# IoT_Indoor_Climate_Sensor-_upgraded.net
KiCad netlist of a schematic drawn in EasyEDA
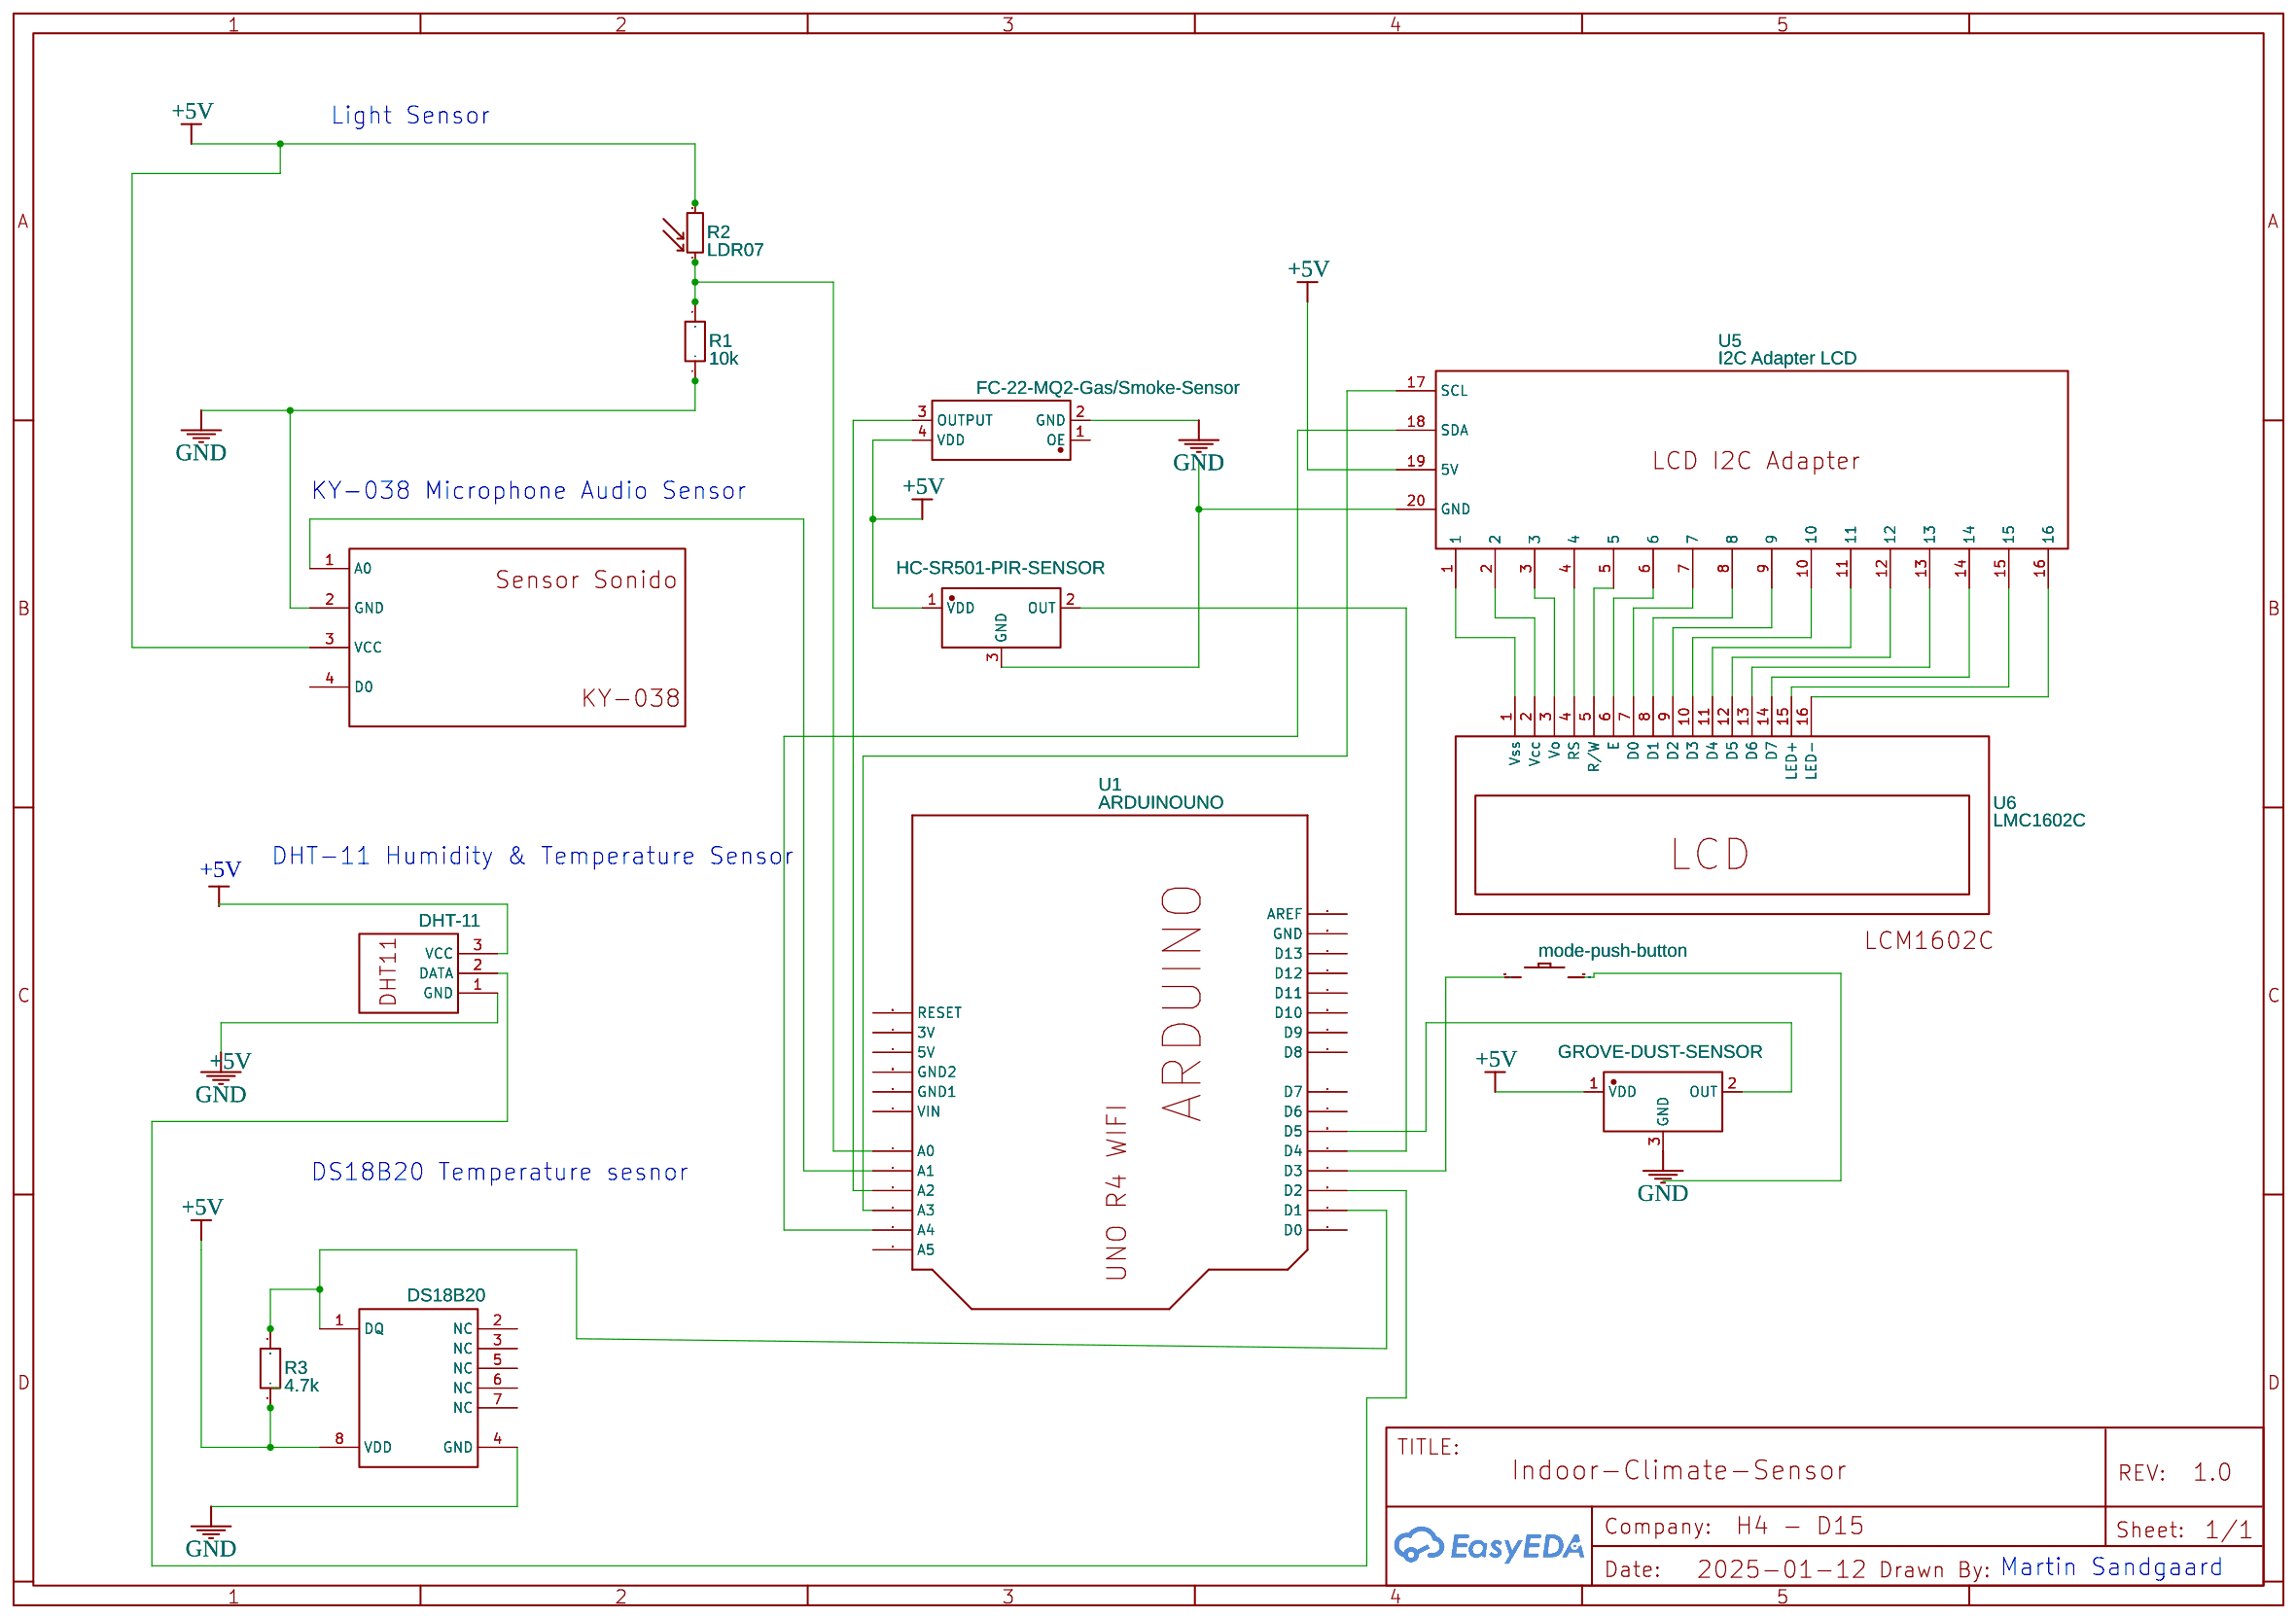
[diagram p0: schematic sheet]

(export (version "E")
  (design (tool "Eeschema 10.0.6"))
  (components
    (comp (ref "1") (value "mode-push-button") (libsource (lib "") (part "button")))
    (comp (ref "GROVE-DUST-SENSOR")
      (value "EKMB1309113K")
      (fields (field (name "Manufacturer") "PANASONIC(松下)"))
      (libsource (lib "") (part "EKMB1309113K_1"))
    )
    (comp (ref "HC-SR501-PIR-SENSOR")
      (value "EKMB1309113K")
      (fields (field (name "Manufacturer") "PANASONIC(松下)"))
      (libsource (lib "") (part "EKMB1309113K"))
    )
    (comp (ref "OSC1")
      (value "FC-22-MQ2-Gas/Smoke-Sensor")
      (fields (field (name "Manufacturer Part") "AMPMDFC-22.0000T3") (field (name "Manufacturer") "ABRACON"))
      (libsource (lib "") (part "AMPMDFC-22.0000T3"))
    )
    (comp (ref "R1") (value "10k") (libsource (lib "") (part "R_0603_EU")))
    (comp (ref "R2") (value "LDR07") (libsource (lib "") (part "LDR07")))
    (comp (ref "R3") (value "4.7k") (libsource (lib "") (part "R_0603_EU")))
    (comp (ref "U1") (value "ARDUINOUNO") (libsource (lib "") (part "ARDUINOUNO")))
    (comp (ref "U2") (value "DS18B20") (libsource (lib "") (part "DS18B20U+")))
    (comp (ref "U3")
      (value "KY-038 Microphone Sound Sensor")
      (libsource (lib "") (part "KY-037 KY038 SENSOR SONIDO COPY"))
    )
    (comp (ref "U4") (value "DHT-11") (libsource (lib "") (part "DHT-11")))
    (comp (ref "U5") (value "I2C Adapter LCD") (libsource (lib "") (part "I2C Adapter LCD")))
    (comp (ref "U6") (value "LMC1602C") (libsource (lib "") (part "LMC1602C")))
  )
  (nets
    (net (code "1") (name "+5V") (class "Default")
      (node (ref "GROVE-DUST-SENSOR") (pin "1") (pinfunction "VDD_1") (pintype "unspecified"))
      (node (ref "HC-SR501-PIR-SENSOR") (pin "1") (pinfunction "VDD_1") (pintype "unspecified"))
      (node (ref "OSC1") (pin "4") (pinfunction "VDD_4") (pintype "unspecified"))
      (node (ref "R2") (pin "1") (pintype "unspecified"))
      (node (ref "R3") (pin "1") (pinfunction "1_1") (pintype "unspecified"))
      (node (ref "U2") (pin "8") (pinfunction "VDD_8") (pintype "passive"))
      (node (ref "U3") (pin "3") (pinfunction "VCC_3") (pintype "unspecified"))
      (node (ref "U4") (pin "3") (pinfunction "VCC_3") (pintype "unspecified"))
      (node (ref "U5") (pin "19") (pinfunction "5V_19") (pintype "unspecified"))
    )
    (net (code "2") (name "GND") (class "Default")
      (node (ref "GROVE-DUST-SENSOR") (pin "3") (pinfunction "GND_3") (pintype "unspecified"))
      (node (ref "OSC1") (pin "2") (pinfunction "GND_2") (pintype "unspecified"))
      (node (ref "R1") (pin "1") (pinfunction "1_1") (pintype "unspecified"))
      (node (ref "U2") (pin "4") (pinfunction "GND_4") (pintype "passive"))
      (node (ref "U3") (pin "2") (pinfunction "GND_2") (pintype "unspecified"))
      (node (ref "U4") (pin "1") (pinfunction "GND_1") (pintype "unspecified"))
    )
    (net (code "3") (name "Net-(1-PadP$GND)") (class "Default")
      (node (ref "1") (pin "P$GND") (pinfunction "P$GND_P$GND") (pintype "unspecified"))
      (node (ref "U1") (pin "D3") (pinfunction "D3_D3") (pintype "unspecified"))
    )
    (net (code "4") (name "Net-(GROVE-DUST-SENSOR-OUT)") (class "Default")
      (node (ref "GROVE-DUST-SENSOR") (pin "2") (pinfunction "OUT_2") (pintype "unspecified"))
      (node (ref "U1") (pin "D5") (pinfunction "D5_D5") (pintype "unspecified"))
    )
    (net (code "5") (name "Net-(HC-SR501-PIR-SENSOR-GND)") (class "Default")
      (node (ref "HC-SR501-PIR-SENSOR") (pin "3") (pinfunction "GND_3") (pintype "unspecified"))
      (node (ref "U5") (pin "20") (pinfunction "GND_20") (pintype "unspecified"))
    )
    (net (code "6") (name "Net-(HC-SR501-PIR-SENSOR-OUT)") (class "Default")
      (node (ref "HC-SR501-PIR-SENSOR") (pin "2") (pinfunction "OUT_2") (pintype "unspecified"))
      (node (ref "U1") (pin "D4") (pinfunction "D4_D4") (pintype "unspecified"))
    )
    (net (code "7") (name "Net-(OSC1-OUTPUT)") (class "Default")
      (node (ref "OSC1") (pin "3") (pinfunction "OUTPUT_3") (pintype "unspecified"))
      (node (ref "U1") (pin "A2") (pinfunction "A2_A2") (pintype "unspecified"))
    )
    (net (code "8") (name "Net-(R1-Pad2)") (class "Default")
      (node (ref "R1") (pin "2") (pinfunction "2_2") (pintype "unspecified"))
      (node (ref "R2") (pin "2") (pintype "unspecified"))
      (node (ref "U1") (pin "A0") (pinfunction "A0_A0") (pintype "unspecified"))
    )
    (net (code "9") (name "Net-(U2-DQ)") (class "Default")
      (node (ref "R3") (pin "2") (pinfunction "2_2") (pintype "unspecified"))
      (node (ref "U1") (pin "D1") (pinfunction "D1_D1") (pintype "unspecified"))
      (node (ref "U2") (pin "1") (pinfunction "DQ_1") (pintype "bidirectional"))
    )
    (net (code "10") (name "Net-(U3-A0)") (class "Default")
      (node (ref "U1") (pin "A1") (pinfunction "A1_A1") (pintype "unspecified"))
      (node (ref "U3") (pin "1") (pinfunction "A0_1") (pintype "unspecified"))
    )
    (net (code "11") (name "Net-(U4-DATA)") (class "Default")
      (node (ref "U1") (pin "D2") (pinfunction "D2_D2") (pintype "unspecified"))
      (node (ref "U4") (pin "2") (pinfunction "DATA_2") (pintype "unspecified"))
    )
    (net (code "12") (name "Net-(U5-SCL)") (class "Default")
      (node (ref "U1") (pin "A3") (pinfunction "A3_A3") (pintype "unspecified"))
      (node (ref "U5") (pin "17") (pinfunction "SCL_17") (pintype "unspecified"))
    )
    (net (code "13") (name "Net-(U5-SDA)") (class "Default")
      (node (ref "U1") (pin "A4") (pinfunction "A4_A4") (pintype "unspecified"))
      (node (ref "U5") (pin "18") (pinfunction "SDA_18") (pintype "unspecified"))
    )
    (net (code "14") (name "Net-(U6-D0)") (class "Default")
      (node (ref "U5") (pin "7") (pinfunction "7_7") (pintype "unspecified"))
      (node (ref "U6") (pin "7") (pinfunction "D0_7") (pintype "unspecified"))
    )
    (net (code "15") (name "Net-(U6-D1)") (class "Default")
      (node (ref "U5") (pin "8") (pinfunction "8_8") (pintype "unspecified"))
      (node (ref "U6") (pin "8") (pinfunction "D1_8") (pintype "unspecified"))
    )
    (net (code "16") (name "Net-(U6-D2)") (class "Default")
      (node (ref "U5") (pin "9") (pinfunction "9_9") (pintype "unspecified"))
      (node (ref "U6") (pin "9") (pinfunction "D2_9") (pintype "unspecified"))
    )
    (net (code "17") (name "Net-(U6-D3)") (class "Default")
      (node (ref "U5") (pin "10") (pinfunction "10_10") (pintype "unspecified"))
      (node (ref "U6") (pin "10") (pinfunction "D3_10") (pintype "unspecified"))
    )
    (net (code "18") (name "Net-(U6-D4)") (class "Default")
      (node (ref "U5") (pin "11") (pinfunction "11_11") (pintype "unspecified"))
      (node (ref "U6") (pin "11") (pinfunction "D4_11") (pintype "unspecified"))
    )
    (net (code "19") (name "Net-(U6-D5)") (class "Default")
      (node (ref "U5") (pin "12") (pinfunction "12_12") (pintype "unspecified"))
      (node (ref "U6") (pin "12") (pinfunction "D5_12") (pintype "unspecified"))
    )
    (net (code "20") (name "Net-(U6-D6)") (class "Default")
      (node (ref "U5") (pin "13") (pinfunction "13_13") (pintype "unspecified"))
      (node (ref "U6") (pin "13") (pinfunction "D6_13") (pintype "unspecified"))
    )
    (net (code "21") (name "Net-(U6-D7)") (class "Default")
      (node (ref "U5") (pin "14") (pinfunction "14_14") (pintype "unspecified"))
      (node (ref "U6") (pin "14") (pinfunction "D7_14") (pintype "unspecified"))
    )
    (net (code "22") (name "Net-(U6-E)") (class "Default")
      (node (ref "U5") (pin "6") (pinfunction "6_6") (pintype "unspecified"))
      (node (ref "U6") (pin "6") (pinfunction "E_6") (pintype "unspecified"))
    )
    (net (code "23") (name "Net-(U6-LED+)") (class "Default")
      (node (ref "U5") (pin "15") (pinfunction "15_15") (pintype "unspecified"))
      (node (ref "U6") (pin "15") (pinfunction "LED+_15") (pintype "unspecified"))
    )
    (net (code "24") (name "Net-(U6-LED-)") (class "Default")
      (node (ref "U5") (pin "16") (pinfunction "16_16") (pintype "unspecified"))
      (node (ref "U6") (pin "16") (pinfunction "LED-_16") (pintype "unspecified"))
    )
    (net (code "25") (name "Net-(U6-RS)") (class "Default")
      (node (ref "U5") (pin "4") (pinfunction "4_4") (pintype "unspecified"))
      (node (ref "U6") (pin "4") (pinfunction "RS_4") (pintype "unspecified"))
    )
    (net (code "26") (name "Net-(U6-R{slash}W)") (class "Default")
      (node (ref "U5") (pin "5") (pinfunction "5_5") (pintype "unspecified"))
      (node (ref "U6") (pin "5") (pinfunction "R/W_5") (pintype "unspecified"))
    )
    (net (code "27") (name "Net-(U6-Vcc)") (class "Default")
      (node (ref "U5") (pin "2") (pinfunction "2_2") (pintype "unspecified"))
      (node (ref "U6") (pin "2") (pinfunction "Vcc_2") (pintype "unspecified"))
    )
    (net (code "28") (name "Net-(U6-Vo)") (class "Default")
      (node (ref "U5") (pin "3") (pinfunction "3_3") (pintype "unspecified"))
      (node (ref "U6") (pin "3") (pinfunction "Vo_3") (pintype "unspecified"))
    )
    (net (code "29") (name "Net-(U6-Vss)") (class "Default")
      (node (ref "U5") (pin "1") (pinfunction "1_1") (pintype "unspecified"))
      (node (ref "U6") (pin "1") (pinfunction "Vss_1") (pintype "unspecified"))
    )
    (net (code "30") (name "unconnected-(1-PadP$ACTIVE)") (class "Default")
      (node (ref "1") (pin "P$ACTIVE") (pinfunction "P$ACTIVE_P$ACTIVE") (pintype "unspecified"))
    )
    (net (code "31") (name "unconnected-(OSC1-OE-Pad1)") (class "Default")
      (node (ref "OSC1") (pin "1") (pinfunction "OE_1") (pintype "unspecified"))
    )
    (net (code "32") (name "unconnected-(U1-Pad3V)") (class "Default")
      (node (ref "U1") (pin "3V") (pinfunction "3V_3V") (pintype "passive"))
    )
    (net (code "33") (name "unconnected-(U1-Pad5V)") (class "Default")
      (node (ref "U1") (pin "5V") (pinfunction "5V_5V") (pintype "passive"))
    )
    (net (code "34") (name "unconnected-(U1-PadA5)") (class "Default")
      (node (ref "U1") (pin "A5") (pinfunction "A5_A5") (pintype "unspecified"))
    )
    (net (code "35") (name "unconnected-(U1-PadAREF)") (class "Default")
      (node (ref "U1") (pin "AREF") (pinfunction "AREF_AREF") (pintype "unspecified"))
    )
    (net (code "36") (name "unconnected-(U1-PadD0)") (class "Default")
      (node (ref "U1") (pin "D0") (pinfunction "D0_D0") (pintype "unspecified"))
    )
    (net (code "37") (name "unconnected-(U1-PadD6)") (class "Default")
      (node (ref "U1") (pin "D6") (pinfunction "D6_D6") (pintype "unspecified"))
    )
    (net (code "38") (name "unconnected-(U1-PadD7)") (class "Default")
      (node (ref "U1") (pin "D7") (pinfunction "D7_D7") (pintype "unspecified"))
    )
    (net (code "39") (name "unconnected-(U1-PadD8)") (class "Default")
      (node (ref "U1") (pin "D8") (pinfunction "D8_D8") (pintype "unspecified"))
    )
    (net (code "40") (name "unconnected-(U1-PadD9)") (class "Default")
      (node (ref "U1") (pin "D9") (pinfunction "D9_D9") (pintype "unspecified"))
    )
    (net (code "41") (name "unconnected-(U1-PadD10)") (class "Default")
      (node (ref "U1") (pin "D10") (pinfunction "D10_D10") (pintype "unspecified"))
    )
    (net (code "42") (name "unconnected-(U1-PadD11)") (class "Default")
      (node (ref "U1") (pin "D11") (pinfunction "D11_D11") (pintype "unspecified"))
    )
    (net (code "43") (name "unconnected-(U1-PadD12)") (class "Default")
      (node (ref "U1") (pin "D12") (pinfunction "D12_D12") (pintype "unspecified"))
    )
    (net (code "44") (name "unconnected-(U1-PadD13)") (class "Default")
      (node (ref "U1") (pin "D13") (pinfunction "D13_D13") (pintype "unspecified"))
    )
    (net (code "45") (name "unconnected-(U1-PadGND)") (class "Default")
      (node (ref "U1") (pin "GND") (pinfunction "GND_GND") (pintype "passive"))
    )
    (net (code "46") (name "unconnected-(U1-PadGND1)") (class "Default")
      (node (ref "U1") (pin "GND1") (pinfunction "GND1_GND1") (pintype "passive"))
    )
    (net (code "47") (name "unconnected-(U1-PadGND2)") (class "Default")
      (node (ref "U1") (pin "GND2") (pinfunction "GND2_GND2") (pintype "passive"))
    )
    (net (code "48") (name "unconnected-(U1-PadRESET)") (class "Default")
      (node (ref "U1") (pin "RESET") (pinfunction "RESET_RESET") (pintype "unspecified"))
    )
    (net (code "49") (name "unconnected-(U1-PadVIN)") (class "Default")
      (node (ref "U1") (pin "VIN") (pinfunction "VIN_VIN") (pintype "passive"))
    )
    (net (code "50") (name "unconnected-(U2-NC-Pad2)") (class "Default")
      (node (ref "U2") (pin "2") (pinfunction "NC_2") (pintype "unspecified"))
    )
    (net (code "51") (name "unconnected-(U2-NC-Pad3)") (class "Default")
      (node (ref "U2") (pin "3") (pinfunction "NC_3") (pintype "unspecified"))
    )
    (net (code "52") (name "unconnected-(U2-NC-Pad5)") (class "Default")
      (node (ref "U2") (pin "5") (pinfunction "NC_5") (pintype "unspecified"))
    )
    (net (code "53") (name "unconnected-(U2-NC-Pad6)") (class "Default")
      (node (ref "U2") (pin "6") (pinfunction "NC_6") (pintype "unspecified"))
    )
    (net (code "54") (name "unconnected-(U2-NC-Pad7)") (class "Default")
      (node (ref "U2") (pin "7") (pinfunction "NC_7") (pintype "unspecified"))
    )
    (net (code "55") (name "unconnected-(U3-D0-Pad4)") (class "Default")
      (node (ref "U3") (pin "4") (pinfunction "D0_4") (pintype "unspecified"))
    )
  )
)
